# LoRa_v01h.net
KiCad netlist of a schematic drawn in EAGLE
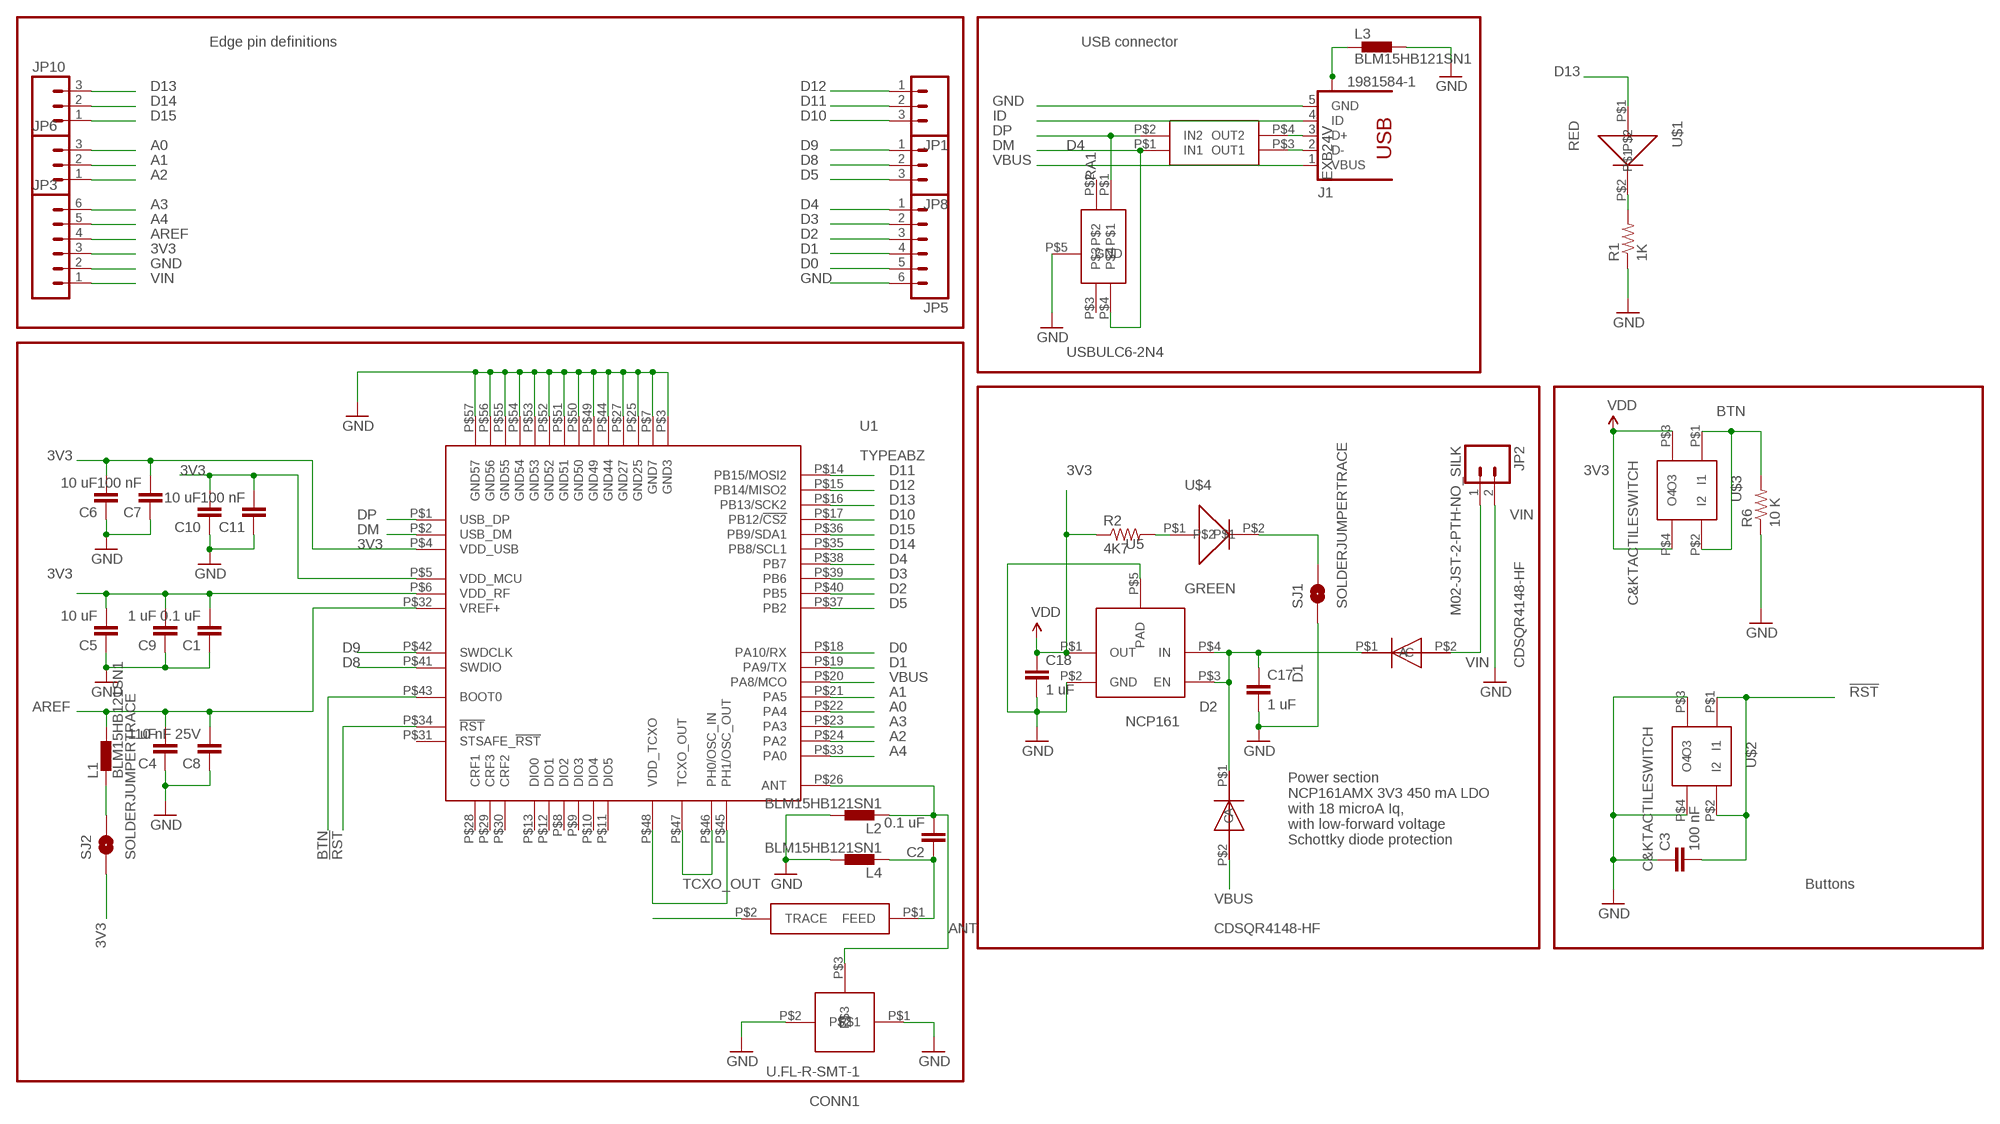
[diagram p0: schematic, sheet 1]

(export (version "E")
  (design (tool "Eeschema 10.0.6"))
  (components
    (comp (ref "C1")
      (value "0.1 uF")
      (footprint "eagle-import:0402-CAP")
      (libsource (lib "eagle-import") (part "0402CAP.KW"))
    )
    (comp (ref "C2")
      (value "0.1 uF")
      (footprint "eagle-import:0402-CAP")
      (libsource (lib "eagle-import") (part "0402CAP.KW"))
    )
    (comp (ref "C3")
      (value "100 nF")
      (footprint "eagle-import:0402-CAP")
      (libsource (lib "eagle-import") (part "0402CAP.KW"))
    )
    (comp (ref "C4")
      (value "1 uF")
      (footprint "eagle-import:0402-CAP")
      (libsource (lib "eagle-import") (part "0402CAP.KW"))
    )
    (comp (ref "C5")
      (value "10 uF")
      (footprint "eagle-import:0402-CAP")
      (libsource (lib "eagle-import") (part "0402CAP.KW"))
    )
    (comp (ref "C6")
      (value "10 uF")
      (footprint "eagle-import:0402-CAP")
      (libsource (lib "eagle-import") (part "0402CAP.KW"))
    )
    (comp (ref "C7")
      (value "100 nF")
      (footprint "eagle-import:0402-CAP")
      (libsource (lib "eagle-import") (part "0402CAP.KW"))
    )
    (comp (ref "C8")
      (value "10 nF 25V")
      (footprint "eagle-import:0402-CAP")
      (libsource (lib "eagle-import") (part "0402CAP.KW"))
    )
    (comp (ref "C9")
      (value "1 uF")
      (footprint "eagle-import:0402-CAP")
      (libsource (lib "eagle-import") (part "0402CAP.KW"))
    )
    (comp (ref "C10")
      (value "10 uF")
      (footprint "eagle-import:0402-CAP")
      (libsource (lib "eagle-import") (part "0402CAP.KW"))
    )
    (comp (ref "C11")
      (value "100 nF")
      (footprint "eagle-import:0402-CAP")
      (libsource (lib "eagle-import") (part "0402CAP.KW"))
    )
    (comp (ref "C17")
      (value "1 uF")
      (footprint "eagle-import:0402-CAP")
      (libsource (lib "eagle-import") (part "0402CAP.KW"))
    )
    (comp (ref "C18")
      (value "1 uF")
      (footprint "eagle-import:0402-CAP")
      (libsource (lib "eagle-import") (part "0402CAP.KW"))
    )
    (comp (ref "CONN1")
      (value "U.FL-R-SMT-1")
      (footprint "eagle-import:U.FL-R-SMT-1")
      (libsource (lib "eagle-import") (part "U.FL-R-SMT-1"))
    )
    (comp (ref "D1")
      (value "CDSQR4148-HF")
      (footprint "eagle-import:CDSQR4148-HF")
      (libsource (lib "eagle-import") (part "CDSQR4148-HF"))
    )
    (comp (ref "D2")
      (value "CDSQR4148-HF")
      (footprint "eagle-import:CDSQR4148-HF")
      (libsource (lib "eagle-import") (part "CDSQR4148-HF"))
    )
    (comp (ref "D4")
      (value "USBULC6-2N4")
      (footprint "eagle-import:USBULC6-2N4")
      (libsource (lib "eagle-import") (part "USBULC6-2N4"))
    )
    (comp (ref "J1")
      (value "1981584-1")
      (footprint "eagle-import:1981584-1")
      (fields (field (name "MF") "Hirose") (field (name "MPN") "ZX62-AB-5PA(11) "))
      (libsource (lib "eagle-import") (part "1981584-1"))
    )
    (comp (ref "JP1")
      (value "M031X03_NO_SILK")
      (footprint "eagle-import:1X03_NO_SILK")
      (libsource (lib "eagle-import") (part "M031X03_NO_SILK"))
    )
    (comp (ref "JP2")
      (value "M02-JST-2-PTH-NO_SILK")
      (footprint "eagle-import:JST-2-PTH-NS")
      (libsource (lib "eagle-import") (part "M02-JST-2-PTH-NO_SILK"))
    )
    (comp (ref "JP3")
      (value "M06NO_SILK")
      (footprint "eagle-import:1X06_NO_SILK")
      (libsource (lib "eagle-import") (part "M06NO_SILK"))
    )
    (comp (ref "JP5")
      (value "M06NO_SILK")
      (footprint "eagle-import:1X06_NO_SILK")
      (libsource (lib "eagle-import") (part "M06NO_SILK"))
    )
    (comp (ref "JP6")
      (value "M031X03_NO_SILK")
      (footprint "eagle-import:1X03_NO_SILK")
      (libsource (lib "eagle-import") (part "M031X03_NO_SILK"))
    )
    (comp (ref "JP8")
      (value "M031X03_NO_SILK")
      (footprint "eagle-import:1X03_NO_SILK")
      (libsource (lib "eagle-import") (part "M031X03_NO_SILK"))
    )
    (comp (ref "JP10")
      (value "M031X03_NO_SILK")
      (footprint "eagle-import:1X03_NO_SILK")
      (libsource (lib "eagle-import") (part "M031X03_NO_SILK"))
    )
    (comp (ref "L1")
      (value "BLM15HB121SN1")
      (footprint "eagle-import:0402")
      (libsource (lib "eagle-import") (part "BLM15HB121SN1"))
    )
    (comp (ref "L2")
      (value "BLM15HB121SN1")
      (footprint "eagle-import:0402")
      (libsource (lib "eagle-import") (part "BLM15HB121SN1"))
    )
    (comp (ref "L3")
      (value "BLM15HB121SN1")
      (footprint "eagle-import:0402")
      (libsource (lib "eagle-import") (part "BLM15HB121SN1"))
    )
    (comp (ref "L4")
      (value "BLM15HB121SN1")
      (footprint "eagle-import:0402")
      (libsource (lib "eagle-import") (part "BLM15HB121SN1"))
    )
    (comp (ref "R1")
      (value "1K")
      (footprint "eagle-import:0402-RES")
      (libsource (lib "eagle-import") (part "0402RES.KW"))
    )
    (comp (ref "R2")
      (value "4K7")
      (footprint "eagle-import:0402-RES")
      (libsource (lib "eagle-import") (part "0402RES.KW"))
    )
    (comp (ref "R6")
      (value "10 K")
      (footprint "eagle-import:0402-RES")
      (libsource (lib "eagle-import") (part "0402RES.KW"))
    )
    (comp (ref "RA1")
      (value "EXB24V")
      (footprint "eagle-import:EXB24V")
      (libsource (lib "eagle-import") (part "EXB24V"))
    )
    (comp (ref "SJ1")
      (value "SOLDERJUMPERTRACE")
      (footprint "eagle-import:SJ_2S-TRACE")
      (libsource (lib "eagle-import") (part "SOLDERJUMPERTRACE"))
    )
    (comp (ref "SJ2")
      (value "SOLDERJUMPERTRACE")
      (footprint "eagle-import:SJ_2S-TRACE")
      (libsource (lib "eagle-import") (part "SOLDERJUMPERTRACE"))
    )
    (comp (ref "U$1")
      (value "RED")
      (footprint "eagle-import:0402LED")
      (libsource (lib "eagle-import") (part "0402LED"))
    )
    (comp (ref "U$2")
      (value "C&KTACTILESWITCH")
      (footprint "eagle-import:C&KTACTILESWITCH")
      (libsource (lib "eagle-import") (part "C&KTACTILESWITCH"))
    )
    (comp (ref "U$3")
      (value "C&KTACTILESWITCH")
      (footprint "eagle-import:C&KTACTILESWITCH")
      (libsource (lib "eagle-import") (part "C&KTACTILESWITCH"))
    )
    (comp (ref "U$4")
      (value "GREEN")
      (footprint "eagle-import:0402LED")
      (libsource (lib "eagle-import") (part "0402LED"))
    )
    (comp (ref "U$5")
      (value "JOHANSON0900AT43A0070")
      (footprint "eagle-import:JOHANSON0900AT43A0070")
      (libsource (lib "eagle-import") (part "JOHANSON0900AT43A0070"))
    )
    (comp (ref "U1")
      (value "TYPEABZ")
      (footprint "eagle-import:TYPEABZ")
      (libsource (lib "eagle-import") (part "TYPEABZ"))
    )
    (comp (ref "U5")
      (value "NCP161")
      (footprint "eagle-import:NCP161")
      (libsource (lib "eagle-import") (part "NCP161"))
    )
  )
  (nets
    (net (code "1") (name "/A0") (class "Default")
      (node (ref "JP6") (pin "3") (pinfunction "3_3") (pintype "passive"))
      (node (ref "U1") (pin "P$22") (pinfunction "PA4_P$22") (pintype "bidirectional"))
    )
    (net (code "2") (name "/A1") (class "Default")
      (node (ref "JP6") (pin "2") (pinfunction "2_2") (pintype "passive"))
      (node (ref "U1") (pin "P$21") (pinfunction "PA5_P$21") (pintype "bidirectional"))
    )
    (net (code "3") (name "/A2") (class "Default")
      (node (ref "JP6") (pin "1") (pinfunction "1_1") (pintype "passive"))
      (node (ref "U1") (pin "P$24") (pinfunction "PA2_P$24") (pintype "bidirectional"))
    )
    (net (code "4") (name "/A3") (class "Default")
      (node (ref "JP3") (pin "6") (pinfunction "6_6") (pintype "passive"))
      (node (ref "U1") (pin "P$23") (pinfunction "PA3_P$23") (pintype "bidirectional"))
    )
    (net (code "5") (name "/A4") (class "Default")
      (node (ref "JP3") (pin "5") (pinfunction "5_5") (pintype "passive"))
      (node (ref "U1") (pin "P$33") (pinfunction "PA0_P$33") (pintype "bidirectional"))
    )
    (net (code "6") (name "/ANT") (class "Default")
      (node (ref "C2") (pin "1") (pinfunction "1_1") (pintype "passive"))
      (node (ref "L4") (pin "1") (pinfunction "1_1") (pintype "passive"))
      (node (ref "U$5") (pin "P$1") (pinfunction "FEED_P$1") (pintype "bidirectional"))
    )
    (net (code "7") (name "/AREF") (class "Default")
      (node (ref "C4") (pin "2") (pinfunction "2_2") (pintype "passive"))
      (node (ref "C8") (pin "2") (pinfunction "2_2") (pintype "passive"))
      (node (ref "JP3") (pin "4") (pinfunction "4_4") (pintype "passive"))
      (node (ref "L1") (pin "2") (pinfunction "2_2") (pintype "passive"))
      (node (ref "U1") (pin "P$32") (pinfunction "VREF+_P$32") (pintype "power_in"))
    )
    (net (code "8") (name "/BTN") (class "Default")
      (node (ref "R6") (pin "2") (pinfunction "2_2") (pintype "passive"))
      (node (ref "U$3") (pin "P$1") (pinfunction "I1_P$1") (pintype "bidirectional"))
      (node (ref "U$3") (pin "P$2") (pinfunction "I2_P$2") (pintype "bidirectional"))
      (node (ref "U1") (pin "P$43") (pinfunction "BOOT0_P$43") (pintype "bidirectional"))
    )
    (net (code "9") (name "/D0") (class "Default")
      (node (ref "JP5") (pin "5") (pinfunction "5_5") (pintype "passive"))
      (node (ref "U1") (pin "P$18") (pinfunction "PA10/RX_P$18") (pintype "bidirectional"))
    )
    (net (code "10") (name "/D1") (class "Default")
      (node (ref "JP5") (pin "4") (pinfunction "4_4") (pintype "passive"))
      (node (ref "U1") (pin "P$19") (pinfunction "PA9/TX_P$19") (pintype "bidirectional"))
    )
    (net (code "11") (name "/D2") (class "Default")
      (node (ref "JP5") (pin "3") (pinfunction "3_3") (pintype "passive"))
      (node (ref "U1") (pin "P$40") (pinfunction "PB5_P$40") (pintype "bidirectional"))
    )
    (net (code "12") (name "/D3") (class "Default")
      (node (ref "JP5") (pin "2") (pinfunction "2_2") (pintype "passive"))
      (node (ref "U1") (pin "P$39") (pinfunction "PB6_P$39") (pintype "bidirectional"))
    )
    (net (code "13") (name "/D4") (class "Default")
      (node (ref "JP5") (pin "1") (pinfunction "1_1") (pintype "passive"))
      (node (ref "U1") (pin "P$38") (pinfunction "PB7_P$38") (pintype "bidirectional"))
    )
    (net (code "14") (name "/D5") (class "Default")
      (node (ref "JP8") (pin "3") (pinfunction "3_3") (pintype "passive"))
      (node (ref "U1") (pin "P$37") (pinfunction "PB2_P$37") (pintype "bidirectional"))
    )
    (net (code "15") (name "/D8") (class "Default")
      (node (ref "JP8") (pin "2") (pinfunction "2_2") (pintype "passive"))
      (node (ref "U1") (pin "P$41") (pinfunction "SWDIO_P$41") (pintype "bidirectional"))
    )
    (net (code "16") (name "/D9") (class "Default")
      (node (ref "JP8") (pin "1") (pinfunction "1_1") (pintype "passive"))
      (node (ref "U1") (pin "P$42") (pinfunction "SWDCLK_P$42") (pintype "bidirectional"))
    )
    (net (code "17") (name "/D10") (class "Default")
      (node (ref "JP1") (pin "3") (pinfunction "3_3") (pintype "passive"))
      (node (ref "U1") (pin "P$17") (pinfunction "PB12/~{CS2}_P$17") (pintype "bidirectional"))
    )
    (net (code "18") (name "/D11") (class "Default")
      (node (ref "JP1") (pin "2") (pinfunction "2_2") (pintype "passive"))
      (node (ref "U1") (pin "P$14") (pinfunction "PB15/MOSI2_P$14") (pintype "bidirectional"))
    )
    (net (code "19") (name "/D12") (class "Default")
      (node (ref "JP1") (pin "1") (pinfunction "1_1") (pintype "passive"))
      (node (ref "U1") (pin "P$15") (pinfunction "PB14/MISO2_P$15") (pintype "bidirectional"))
    )
    (net (code "20") (name "/D13") (class "Default")
      (node (ref "JP10") (pin "3") (pinfunction "3_3") (pintype "passive"))
      (node (ref "U$1") (pin "P$1") (pinfunction "P$1_P$1") (pintype "bidirectional"))
      (node (ref "U1") (pin "P$16") (pinfunction "PB13/SCK2_P$16") (pintype "bidirectional"))
    )
    (net (code "21") (name "/D14") (class "Default")
      (node (ref "JP10") (pin "2") (pinfunction "2_2") (pintype "passive"))
      (node (ref "U1") (pin "P$35") (pinfunction "PB8/SCL1_P$35") (pintype "bidirectional"))
    )
    (net (code "22") (name "/D15") (class "Default")
      (node (ref "JP10") (pin "1") (pinfunction "1_1") (pintype "passive"))
      (node (ref "U1") (pin "P$36") (pinfunction "PB9/SDA1_P$36") (pintype "bidirectional"))
    )
    (net (code "23") (name "/DM") (class "Default")
      (node (ref "D4") (pin "P$4") (pinfunction "P$4_P$4") (pintype "bidirectional"))
      (node (ref "RA1") (pin "P$1") (pinfunction "IN1_P$1") (pintype "bidirectional"))
      (node (ref "U1") (pin "P$2") (pinfunction "USB_DM_P$2") (pintype "bidirectional"))
    )
    (net (code "24") (name "/DP") (class "Default")
      (node (ref "D4") (pin "P$1") (pinfunction "P$1_P$1") (pintype "bidirectional"))
      (node (ref "RA1") (pin "P$2") (pinfunction "IN2_P$2") (pintype "bidirectional"))
      (node (ref "U1") (pin "P$1") (pinfunction "USB_DP_P$1") (pintype "bidirectional"))
    )
    (net (code "25") (name "/ID") (class "Default")
      (node (ref "J1") (pin "4") (pinfunction "ID_4") (pintype "passive"))
    )
    (net (code "26") (name "/TCXO_OUT") (class "Default")
      (node (ref "U1") (pin "P$46") (pinfunction "PH0/OSC_IN_P$46") (pintype "bidirectional"))
      (node (ref "U1") (pin "P$47") (pinfunction "TCXO_OUT_P$47") (pintype "bidirectional"))
    )
    (net (code "27") (name "/VBUS") (class "Default")
      (node (ref "D2") (pin "P$2") (pinfunction "A_P$2") (pintype "bidirectional"))
      (node (ref "J1") (pin "1") (pinfunction "VBUS_1") (pintype "passive"))
      (node (ref "U1") (pin "P$20") (pinfunction "PA8/MCO_P$20") (pintype "bidirectional"))
    )
    (net (code "28") (name "/VIN") (class "Default")
      (node (ref "D1") (pin "P$2") (pinfunction "A_P$2") (pintype "bidirectional"))
      (node (ref "JP2") (pin "1") (pinfunction "1_1") (pintype "passive"))
      (node (ref "JP3") (pin "1") (pinfunction "1_1") (pintype "passive"))
    )
    (net (code "29") (name "/~{RST}") (class "Default")
      (node (ref "C3") (pin "2") (pinfunction "2_2") (pintype "passive"))
      (node (ref "U$2") (pin "P$1") (pinfunction "I1_P$1") (pintype "bidirectional"))
      (node (ref "U$2") (pin "P$2") (pinfunction "I2_P$2") (pintype "bidirectional"))
      (node (ref "U1") (pin "P$34") (pinfunction "~{RST}_P$34") (pintype "bidirectional"))
    )
    (net (code "30") (name "GND") (class "Default")
      (node (ref "C1") (pin "1") (pinfunction "1_1") (pintype "passive"))
      (node (ref "C10") (pin "1") (pinfunction "1_1") (pintype "passive"))
      (node (ref "C11") (pin "1") (pinfunction "1_1") (pintype "passive"))
      (node (ref "C17") (pin "2") (pinfunction "2_2") (pintype "passive"))
      (node (ref "C18") (pin "2") (pinfunction "2_2") (pintype "passive"))
      (node (ref "C3") (pin "1") (pinfunction "1_1") (pintype "passive"))
      (node (ref "C4") (pin "1") (pinfunction "1_1") (pintype "passive"))
      (node (ref "C5") (pin "1") (pinfunction "1_1") (pintype "passive"))
      (node (ref "C6") (pin "1") (pinfunction "1_1") (pintype "passive"))
      (node (ref "C7") (pin "1") (pinfunction "1_1") (pintype "passive"))
      (node (ref "C8") (pin "1") (pinfunction "1_1") (pintype "passive"))
      (node (ref "C9") (pin "1") (pinfunction "1_1") (pintype "passive"))
      (node (ref "CONN1") (pin "P$1") (pinfunction "P$1_P$1") (pintype "power_in"))
      (node (ref "CONN1") (pin "P$2") (pinfunction "P$2_P$2") (pintype "power_in"))
      (node (ref "D4") (pin "P$5") (pinfunction "GND_P$5") (pintype "bidirectional"))
      (node (ref "J1") (pin "5") (pinfunction "GND_5") (pintype "passive"))
      (node (ref "JP2") (pin "2") (pinfunction "2_2") (pintype "passive"))
      (node (ref "JP3") (pin "2") (pinfunction "2_2") (pintype "passive"))
      (node (ref "JP5") (pin "6") (pinfunction "6_6") (pintype "passive"))
      (node (ref "L2") (pin "2") (pinfunction "2_2") (pintype "passive"))
      (node (ref "L3") (pin "2") (pinfunction "2_2") (pintype "passive"))
      (node (ref "L4") (pin "2") (pinfunction "2_2") (pintype "passive"))
      (node (ref "R1") (pin "1") (pinfunction "1_1") (pintype "passive"))
      (node (ref "R6") (pin "1") (pinfunction "1_1") (pintype "passive"))
      (node (ref "SJ1") (pin "1") (pinfunction "1_1") (pintype "passive"))
      (node (ref "U$2") (pin "P$3") (pinfunction "O3_P$3") (pintype "bidirectional"))
      (node (ref "U$2") (pin "P$4") (pinfunction "O4_P$4") (pintype "bidirectional"))
      (node (ref "U1") (pin "P$25") (pinfunction "GND25_P$25") (pintype "power_in"))
      (node (ref "U1") (pin "P$27") (pinfunction "GND27_P$27") (pintype "power_in"))
      (node (ref "U1") (pin "P$3") (pinfunction "GND3_P$3") (pintype "power_in"))
      (node (ref "U1") (pin "P$44") (pinfunction "GND44_P$44") (pintype "power_in"))
      (node (ref "U1") (pin "P$49") (pinfunction "GND49_P$49") (pintype "power_in"))
      (node (ref "U1") (pin "P$50") (pinfunction "GND50_P$50") (pintype "power_in"))
      (node (ref "U1") (pin "P$51") (pinfunction "GND51_P$51") (pintype "power_in"))
      (node (ref "U1") (pin "P$52") (pinfunction "GND52_P$52") (pintype "power_in"))
      (node (ref "U1") (pin "P$53") (pinfunction "GND53_P$53") (pintype "power_in"))
      (node (ref "U1") (pin "P$54") (pinfunction "GND54_P$54") (pintype "power_in"))
      (node (ref "U1") (pin "P$55") (pinfunction "GND55_P$55") (pintype "power_in"))
      (node (ref "U1") (pin "P$56") (pinfunction "GND56_P$56") (pintype "power_in"))
      (node (ref "U1") (pin "P$57") (pinfunction "GND57_P$57") (pintype "power_in"))
      (node (ref "U1") (pin "P$7") (pinfunction "GND7_P$7") (pintype "power_in"))
      (node (ref "U5") (pin "P$2") (pinfunction "GND_P$2") (pintype "power_in"))
      (node (ref "U5") (pin "P$5") (pinfunction "PAD_P$5") (pintype "power_in"))
    )
    (net (code "31") (name "Net-(D1-C)") (class "Default")
      (node (ref "C17") (pin "1") (pinfunction "1_1") (pintype "passive"))
      (node (ref "D1") (pin "P$1") (pinfunction "C_P$1") (pintype "bidirectional"))
      (node (ref "D2") (pin "P$1") (pinfunction "C_P$1") (pintype "bidirectional"))
      (node (ref "U5") (pin "P$3") (pinfunction "EN_P$3") (pintype "bidirectional"))
      (node (ref "U5") (pin "P$4") (pinfunction "IN_P$4") (pintype "power_in"))
    )
    (net (code "32") (name "Net-(J1-D+)") (class "Default")
      (node (ref "J1") (pin "3") (pinfunction "D+_3") (pintype "passive"))
      (node (ref "RA1") (pin "P$4") (pinfunction "OUT2_P$4") (pintype "bidirectional"))
    )
    (net (code "33") (name "Net-(J1-D-)") (class "Default")
      (node (ref "J1") (pin "2") (pinfunction "D-_2") (pintype "passive"))
      (node (ref "RA1") (pin "P$3") (pinfunction "OUT1_P$3") (pintype "bidirectional"))
    )
    (net (code "34") (name "Net-(J1-PadS1)") (class "Default")
      (node (ref "J1") (pin "S1") (pinfunction "S1_S1") (pintype "passive"))
      (node (ref "J1") (pin "S2") (pinfunction "S2_S2") (pintype "passive"))
      (node (ref "J1") (pin "S3") (pinfunction "S3_S3") (pintype "passive"))
      (node (ref "J1") (pin "S4") (pinfunction "S4_S4") (pintype "passive"))
      (node (ref "L3") (pin "1") (pinfunction "1_1") (pintype "passive"))
    )
    (net (code "35") (name "Net-(L1-Pad1)") (class "Default")
      (node (ref "L1") (pin "1") (pinfunction "1_1") (pintype "passive"))
      (node (ref "SJ2") (pin "2") (pinfunction "2_2") (pintype "passive"))
    )
    (net (code "36") (name "Net-(R1-Pad2)") (class "Default")
      (node (ref "R1") (pin "2") (pinfunction "2_2") (pintype "passive"))
      (node (ref "U$1") (pin "P$2") (pinfunction "P$2_P$2") (pintype "bidirectional"))
    )
    (net (code "37") (name "Net-(R2-Pad2)") (class "Default")
      (node (ref "R2") (pin "2") (pinfunction "2_2") (pintype "passive"))
      (node (ref "U$4") (pin "P$1") (pinfunction "P$1_P$1") (pintype "bidirectional"))
    )
    (net (code "38") (name "Net-(SJ1-Pad2)") (class "Default")
      (node (ref "SJ1") (pin "2") (pinfunction "2_2") (pintype "passive"))
      (node (ref "U$4") (pin "P$2") (pinfunction "P$2_P$2") (pintype "bidirectional"))
    )
    (net (code "39") (name "Net-(U1-ANT)") (class "Default")
      (node (ref "C2") (pin "2") (pinfunction "2_2") (pintype "passive"))
      (node (ref "CONN1") (pin "P$3") (pinfunction "P$3_P$3") (pintype "bidirectional"))
      (node (ref "L2") (pin "1") (pinfunction "1_1") (pintype "passive"))
      (node (ref "U1") (pin "P$26") (pinfunction "ANT_P$26") (pintype "bidirectional"))
    )
    (net (code "40") (name "Net-(U1-PH1{slash}OSC_OUT)") (class "Default")
      (node (ref "U1") (pin "P$45") (pinfunction "PH1/OSC_OUT_P$45") (pintype "bidirectional"))
      (node (ref "U1") (pin "P$48") (pinfunction "VDD_TCXO_P$48") (pintype "power_in"))
    )
    (net (code "41") (name "VDD") (class "Default")
      (node (ref "C1") (pin "2") (pinfunction "2_2") (pintype "passive"))
      (node (ref "C10") (pin "2") (pinfunction "2_2") (pintype "passive"))
      (node (ref "C11") (pin "2") (pinfunction "2_2") (pintype "passive"))
      (node (ref "C18") (pin "1") (pinfunction "1_1") (pintype "passive"))
      (node (ref "C5") (pin "2") (pinfunction "2_2") (pintype "passive"))
      (node (ref "C6") (pin "2") (pinfunction "2_2") (pintype "passive"))
      (node (ref "C7") (pin "2") (pinfunction "2_2") (pintype "passive"))
      (node (ref "C9") (pin "2") (pinfunction "2_2") (pintype "passive"))
      (node (ref "JP3") (pin "3") (pinfunction "3_3") (pintype "passive"))
      (node (ref "R2") (pin "1") (pinfunction "1_1") (pintype "passive"))
      (node (ref "SJ2") (pin "1") (pinfunction "1_1") (pintype "passive"))
      (node (ref "U$3") (pin "P$3") (pinfunction "O3_P$3") (pintype "bidirectional"))
      (node (ref "U$3") (pin "P$4") (pinfunction "O4_P$4") (pintype "bidirectional"))
      (node (ref "U1") (pin "P$4") (pinfunction "VDD_USB_P$4") (pintype "power_in"))
      (node (ref "U1") (pin "P$5") (pinfunction "VDD_MCU_P$5") (pintype "power_in"))
      (node (ref "U1") (pin "P$6") (pinfunction "VDD_RF_P$6") (pintype "power_in"))
      (node (ref "U5") (pin "P$1") (pinfunction "OUT_P$1") (pintype "power_in"))
    )
    (net (code "42") (name "unconnected-(D4-PadP$2)") (class "Default")
      (node (ref "D4") (pin "P$2") (pinfunction "P$2_P$2") (pintype "bidirectional"))
    )
    (net (code "43") (name "unconnected-(D4-PadP$3)") (class "Default")
      (node (ref "D4") (pin "P$3") (pinfunction "P$3_P$3") (pintype "bidirectional"))
    )
    (net (code "44") (name "unconnected-(U$5-TRACE-PadP$2)") (class "Default")
      (node (ref "U$5") (pin "P$2") (pinfunction "TRACE_P$2") (pintype "bidirectional"))
    )
    (net (code "45") (name "unconnected-(U1-CRF1-PadP$28)") (class "Default")
      (node (ref "U1") (pin "P$28") (pinfunction "CRF1_P$28") (pintype "no_connect"))
    )
    (net (code "46") (name "unconnected-(U1-CRF2-PadP$30)") (class "Default")
      (node (ref "U1") (pin "P$30") (pinfunction "CRF2_P$30") (pintype "no_connect"))
    )
    (net (code "47") (name "unconnected-(U1-CRF3-PadP$29)") (class "Default")
      (node (ref "U1") (pin "P$29") (pinfunction "CRF3_P$29") (pintype "no_connect"))
    )
    (net (code "48") (name "unconnected-(U1-DIO0-PadP$13)") (class "Default")
      (node (ref "U1") (pin "P$13") (pinfunction "DIO0_P$13") (pintype "no_connect"))
    )
    (net (code "49") (name "unconnected-(U1-DIO1-PadP$12)") (class "Default")
      (node (ref "U1") (pin "P$12") (pinfunction "DIO1_P$12") (pintype "no_connect"))
    )
    (net (code "50") (name "unconnected-(U1-DIO2-PadP$8)") (class "Default")
      (node (ref "U1") (pin "P$8") (pinfunction "DIO2_P$8") (pintype "no_connect"))
    )
    (net (code "51") (name "unconnected-(U1-DIO3-PadP$9)") (class "Default")
      (node (ref "U1") (pin "P$9") (pinfunction "DIO3_P$9") (pintype "no_connect"))
    )
    (net (code "52") (name "unconnected-(U1-DIO4-PadP$10)") (class "Default")
      (node (ref "U1") (pin "P$10") (pinfunction "DIO4_P$10") (pintype "bidirectional"))
    )
    (net (code "53") (name "unconnected-(U1-DIO5-PadP$11)") (class "Default")
      (node (ref "U1") (pin "P$11") (pinfunction "DIO5_P$11") (pintype "bidirectional"))
    )
    (net (code "54") (name "unconnected-(U1-STSAFE_~{RST}-PadP$31)") (class "Default")
      (node (ref "U1") (pin "P$31") (pinfunction "STSAFE_~{RST}_P$31") (pintype "bidirectional"))
    )
  )
)
